# Filter7.net
KiCad netlist of a schematic drawn in Altium Designer
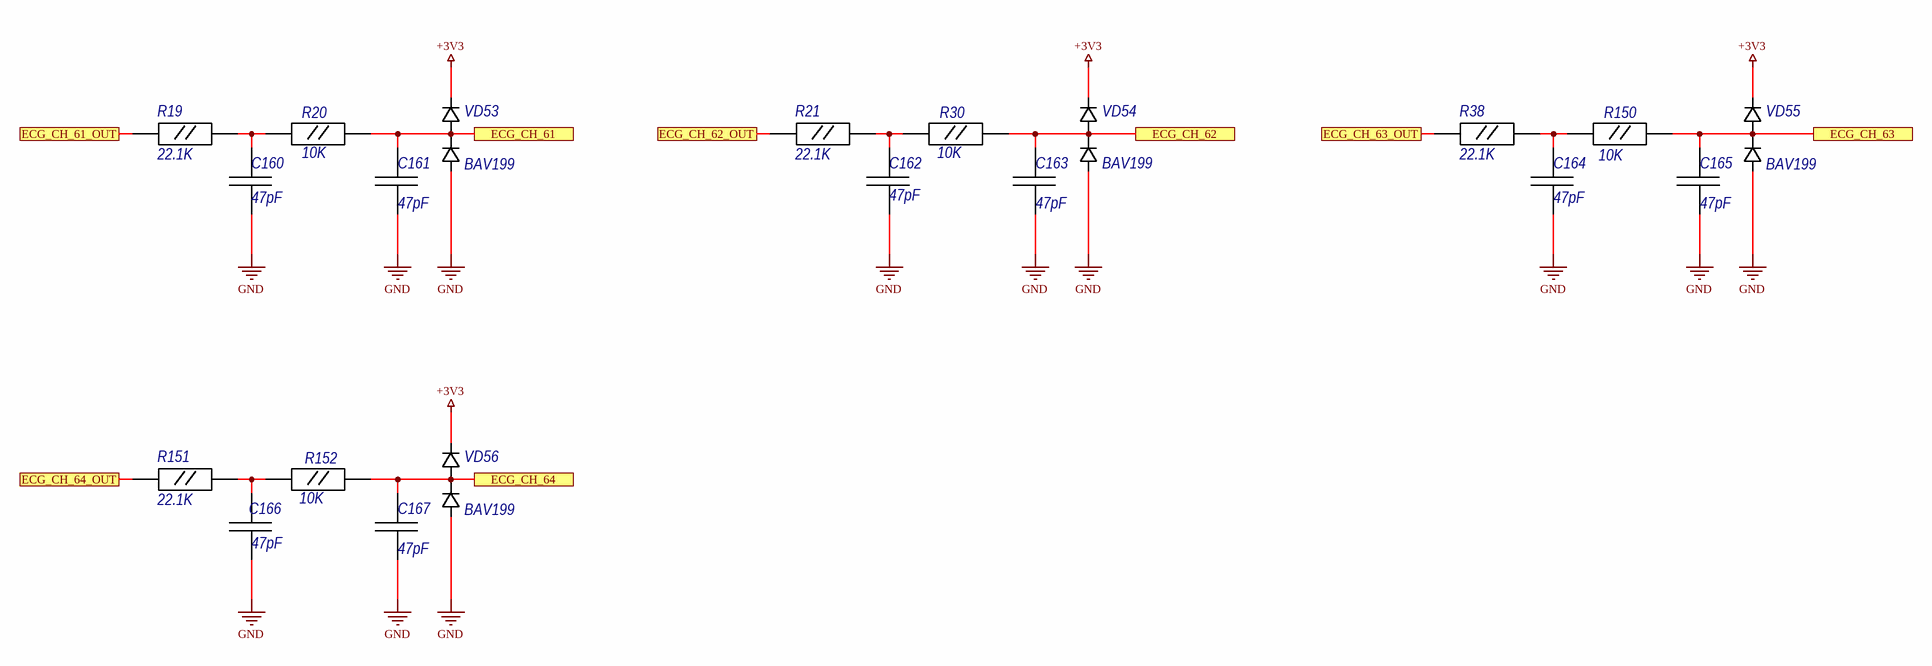
[diagram p0: Filter7.SchDoc]

(export (version "E")
  (design (tool "Eeschema 10.0.6"))
  (components
    (comp (ref "C160")
      (value "47pF")
      (footprint "C0603")
      (description "Ceramic Capacitor SMD")
      (libsource (lib "GOST") (part "CC_SMD_0603"))
    )
    (comp (ref "C161")
      (value "47pF")
      (footprint "C0603")
      (description "Ceramic Capacitor SMD")
      (libsource (lib "GOST") (part "CC_SMD_0603"))
    )
    (comp (ref "C162")
      (value "47pF")
      (footprint "C0603")
      (description "Ceramic Capacitor SMD")
      (libsource (lib "GOST") (part "CC_SMD_0603"))
    )
    (comp (ref "C163")
      (value "47pF")
      (footprint "C0603")
      (description "Ceramic Capacitor SMD")
      (libsource (lib "GOST") (part "CC_SMD_0603"))
    )
    (comp (ref "C164")
      (value "47pF")
      (footprint "C0603")
      (description "Ceramic Capacitor SMD")
      (libsource (lib "GOST") (part "CC_SMD_0603"))
    )
    (comp (ref "C165")
      (value "47pF")
      (footprint "C0603")
      (description "Ceramic Capacitor SMD")
      (libsource (lib "GOST") (part "CC_SMD_0603"))
    )
    (comp (ref "C166")
      (value "47pF")
      (footprint "C0603")
      (description "Ceramic Capacitor SMD")
      (libsource (lib "GOST") (part "CC_SMD_0603"))
    )
    (comp (ref "C167")
      (value "47pF")
      (footprint "C0603")
      (description "Ceramic Capacitor SMD")
      (libsource (lib "GOST") (part "CC_SMD_0603"))
    )
    (comp (ref "R19")
      (value "22.1K")
      (footprint "R0603")
      (description "Resistor SMD")
      (libsource (lib "GOST") (part "R0603"))
    )
    (comp (ref "R20")
      (value "10K")
      (footprint "R0603")
      (description "Resistor SMD")
      (libsource (lib "GOST") (part "R0603"))
    )
    (comp (ref "R21")
      (value "22.1K")
      (footprint "R0603")
      (description "Resistor SMD")
      (libsource (lib "GOST") (part "R0603"))
    )
    (comp (ref "R30")
      (value "10K")
      (footprint "R0603")
      (description "Resistor SMD")
      (libsource (lib "GOST") (part "R0603"))
    )
    (comp (ref "R38")
      (value "22.1K")
      (footprint "R0603")
      (description "Resistor SMD")
      (libsource (lib "GOST") (part "R0603"))
    )
    (comp (ref "R150")
      (value "10K")
      (footprint "R0603")
      (description "Resistor SMD")
      (libsource (lib "GOST") (part "R0603"))
    )
    (comp (ref "R151")
      (value "22.1K")
      (footprint "R0603")
      (description "Resistor SMD")
      (libsource (lib "GOST") (part "R0603"))
    )
    (comp (ref "R152")
      (value "10K")
      (footprint "R0603")
      (description "Resistor SMD")
      (libsource (lib "GOST") (part "R0603"))
    )
    (comp (ref "VD53")
      (value "BAV199")
      (footprint "SOT23")
      (description "Diod Schottky")
      (fields (field (name "MANUFACTURER PART NUMBER 1") "BAV199"))
      (libsource (lib "GOST") (part "DIODE_BAV199"))
    )
    (comp (ref "VD54")
      (value "BAV199")
      (footprint "SOT23")
      (description "Diod Schottky")
      (fields (field (name "MANUFACTURER PART NUMBER 1") "BAV199"))
      (libsource (lib "GOST") (part "DIODE_BAV199"))
    )
    (comp (ref "VD55")
      (value "BAV199")
      (footprint "SOT23")
      (description "Diod Schottky")
      (fields (field (name "MANUFACTURER PART NUMBER 1") "BAV199"))
      (libsource (lib "GOST") (part "DIODE_BAV199"))
    )
    (comp (ref "VD56")
      (value "BAV199")
      (footprint "SOT23")
      (description "Diod Schottky")
      (fields (field (name "MANUFACTURER PART NUMBER 1") "BAV199"))
      (libsource (lib "GOST") (part "DIODE_BAV199"))
    )
  )
  (nets
    (net (code "1") (name "+3V3") (class "Default")
      (node (ref "VD53") (pin "2") (pinfunction "2_2") (pintype "passive"))
      (node (ref "VD54") (pin "2") (pinfunction "2_2") (pintype "passive"))
      (node (ref "VD55") (pin "2") (pinfunction "2_2") (pintype "passive"))
      (node (ref "VD56") (pin "2") (pinfunction "2_2") (pintype "passive"))
    )
    (net (code "2") (name "/ECG_CH_61") (class "Default")
      (node (ref "C161") (pin "2") (pinfunction "2_2") (pintype "passive"))
      (node (ref "R20") (pin "2") (pinfunction "2_2") (pintype "passive"))
      (node (ref "VD53") (pin "3") (pinfunction "3_3") (pintype "passive"))
    )
    (net (code "3") (name "/ECG_CH_61_OUT") (class "Default")
      (node (ref "R19") (pin "1") (pinfunction "1_1") (pintype "passive"))
    )
    (net (code "4") (name "/ECG_CH_62") (class "Default")
      (node (ref "C163") (pin "2") (pinfunction "2_2") (pintype "passive"))
      (node (ref "R30") (pin "2") (pinfunction "2_2") (pintype "passive"))
      (node (ref "VD54") (pin "3") (pinfunction "3_3") (pintype "passive"))
    )
    (net (code "5") (name "/ECG_CH_62_OUT") (class "Default")
      (node (ref "R21") (pin "1") (pinfunction "1_1") (pintype "passive"))
    )
    (net (code "6") (name "/ECG_CH_63") (class "Default")
      (node (ref "C165") (pin "2") (pinfunction "2_2") (pintype "passive"))
      (node (ref "R150") (pin "2") (pinfunction "2_2") (pintype "passive"))
      (node (ref "VD55") (pin "3") (pinfunction "3_3") (pintype "passive"))
    )
    (net (code "7") (name "/ECG_CH_63_OUT") (class "Default")
      (node (ref "R38") (pin "1") (pinfunction "1_1") (pintype "passive"))
    )
    (net (code "8") (name "/ECG_CH_64") (class "Default")
      (node (ref "C167") (pin "2") (pinfunction "2_2") (pintype "passive"))
      (node (ref "R152") (pin "2") (pinfunction "2_2") (pintype "passive"))
      (node (ref "VD56") (pin "3") (pinfunction "3_3") (pintype "passive"))
    )
    (net (code "9") (name "/ECG_CH_64_OUT") (class "Default")
      (node (ref "R151") (pin "1") (pinfunction "1_1") (pintype "passive"))
    )
    (net (code "10") (name "GND") (class "Default")
      (node (ref "C160") (pin "1") (pinfunction "1_1") (pintype "passive"))
      (node (ref "C161") (pin "1") (pinfunction "1_1") (pintype "passive"))
      (node (ref "C162") (pin "1") (pinfunction "1_1") (pintype "passive"))
      (node (ref "C163") (pin "1") (pinfunction "1_1") (pintype "passive"))
      (node (ref "C164") (pin "1") (pinfunction "1_1") (pintype "passive"))
      (node (ref "C165") (pin "1") (pinfunction "1_1") (pintype "passive"))
      (node (ref "C166") (pin "1") (pinfunction "1_1") (pintype "passive"))
      (node (ref "C167") (pin "1") (pinfunction "1_1") (pintype "passive"))
      (node (ref "VD53") (pin "1") (pinfunction "1_1") (pintype "passive"))
      (node (ref "VD54") (pin "1") (pinfunction "1_1") (pintype "passive"))
      (node (ref "VD55") (pin "1") (pinfunction "1_1") (pintype "passive"))
      (node (ref "VD56") (pin "1") (pinfunction "1_1") (pintype "passive"))
    )
    (net (code "11") (name "Net-(C160-Pad2)") (class "Default")
      (node (ref "C160") (pin "2") (pinfunction "2_2") (pintype "passive"))
      (node (ref "R19") (pin "2") (pinfunction "2_2") (pintype "passive"))
      (node (ref "R20") (pin "1") (pinfunction "1_1") (pintype "passive"))
    )
    (net (code "12") (name "Net-(C162-Pad2)") (class "Default")
      (node (ref "C162") (pin "2") (pinfunction "2_2") (pintype "passive"))
      (node (ref "R21") (pin "2") (pinfunction "2_2") (pintype "passive"))
      (node (ref "R30") (pin "1") (pinfunction "1_1") (pintype "passive"))
    )
    (net (code "13") (name "Net-(C164-Pad2)") (class "Default")
      (node (ref "C164") (pin "2") (pinfunction "2_2") (pintype "passive"))
      (node (ref "R150") (pin "1") (pinfunction "1_1") (pintype "passive"))
      (node (ref "R38") (pin "2") (pinfunction "2_2") (pintype "passive"))
    )
    (net (code "14") (name "Net-(C166-Pad2)") (class "Default")
      (node (ref "C166") (pin "2") (pinfunction "2_2") (pintype "passive"))
      (node (ref "R151") (pin "2") (pinfunction "2_2") (pintype "passive"))
      (node (ref "R152") (pin "1") (pinfunction "1_1") (pintype "passive"))
    )
  )
)
